# Top_Level.net
KiCad netlist of a schematic drawn in Altium Designer
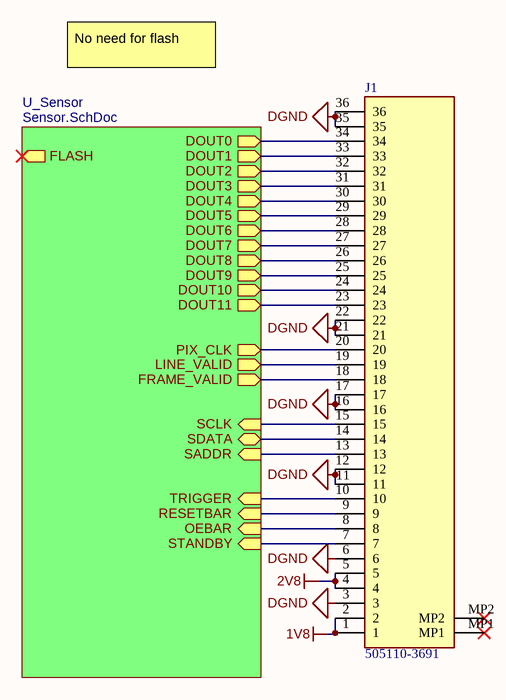
[diagram p0: Top Level.SchDoc]

(export (version "E")
  (design (tool "Eeschema 10.0.6"))
  (components
    (comp (ref "J1")
      (value "505110-3691")
      (footprint "C2Sv0.1:5051103691")
      (description "Connector")
      (libsource (lib "*") (part "505110-3691"))
    )
  )
  (nets
    (net (code "1") (name "/DOUT0") (class "Default")
      (node (ref "J1") (pin "34") (pinfunction "34_34") (pintype "passive"))
    )
    (net (code "2") (name "/DOUT1") (class "Default")
      (node (ref "J1") (pin "33") (pinfunction "33_33") (pintype "passive"))
    )
    (net (code "3") (name "/DOUT2") (class "Default")
      (node (ref "J1") (pin "32") (pinfunction "32_32") (pintype "passive"))
    )
    (net (code "4") (name "/DOUT3") (class "Default")
      (node (ref "J1") (pin "31") (pinfunction "31_31") (pintype "passive"))
    )
    (net (code "5") (name "/DOUT4") (class "Default")
      (node (ref "J1") (pin "30") (pinfunction "30_30") (pintype "passive"))
    )
    (net (code "6") (name "/DOUT5") (class "Default")
      (node (ref "J1") (pin "29") (pinfunction "29_29") (pintype "passive"))
    )
    (net (code "7") (name "/DOUT6") (class "Default")
      (node (ref "J1") (pin "28") (pinfunction "28_28") (pintype "passive"))
    )
    (net (code "8") (name "/DOUT7") (class "Default")
      (node (ref "J1") (pin "27") (pinfunction "27_27") (pintype "passive"))
    )
    (net (code "9") (name "/DOUT8") (class "Default")
      (node (ref "J1") (pin "26") (pinfunction "26_26") (pintype "passive"))
    )
    (net (code "10") (name "/DOUT9") (class "Default")
      (node (ref "J1") (pin "25") (pinfunction "25_25") (pintype "passive"))
    )
    (net (code "11") (name "/DOUT10") (class "Default")
      (node (ref "J1") (pin "24") (pinfunction "24_24") (pintype "passive"))
    )
    (net (code "12") (name "/DOUT11") (class "Default")
      (node (ref "J1") (pin "23") (pinfunction "23_23") (pintype "passive"))
    )
    (net (code "14") (name "/FRAME_VALID") (class "Default")
      (node (ref "J1") (pin "18") (pinfunction "18_18") (pintype "passive"))
    )
    (net (code "15") (name "/LINE_VALID") (class "Default")
      (node (ref "J1") (pin "19") (pinfunction "19_19") (pintype "passive"))
    )
    (net (code "16") (name "/OEBAR") (class "Default")
      (node (ref "J1") (pin "8") (pinfunction "8_8") (pintype "passive"))
    )
    (net (code "17") (name "/PIX_CLK") (class "Default")
      (node (ref "J1") (pin "20") (pinfunction "20_20") (pintype "passive"))
    )
    (net (code "18") (name "/RESETBAR") (class "Default")
      (node (ref "J1") (pin "9") (pinfunction "9_9") (pintype "passive"))
    )
    (net (code "19") (name "/SADDR") (class "Default")
      (node (ref "J1") (pin "13") (pinfunction "13_13") (pintype "passive"))
    )
    (net (code "20") (name "/SCLK") (class "Default")
      (node (ref "J1") (pin "15") (pinfunction "15_15") (pintype "passive"))
    )
    (net (code "21") (name "/SDATA") (class "Default")
      (node (ref "J1") (pin "14") (pinfunction "14_14") (pintype "passive"))
    )
    (net (code "22") (name "/STANDBY") (class "Default")
      (node (ref "J1") (pin "7") (pinfunction "7_7") (pintype "passive"))
    )
    (net (code "23") (name "/TRIGGER") (class "Default")
      (node (ref "J1") (pin "10") (pinfunction "10_10") (pintype "passive"))
    )
    (net (code "24") (name "1V8") (class "Default")
      (node (ref "J1") (pin "1") (pinfunction "1_1") (pintype "passive"))
      (node (ref "J1") (pin "2") (pinfunction "2_2") (pintype "passive"))
    )
    (net (code "25") (name "2V8") (class "Default")
      (node (ref "J1") (pin "4") (pinfunction "4_4") (pintype "passive"))
      (node (ref "J1") (pin "5") (pinfunction "5_5") (pintype "passive"))
    )
    (net (code "26") (name "DGND") (class "Default")
      (node (ref "J1") (pin "11") (pinfunction "11_11") (pintype "passive"))
      (node (ref "J1") (pin "12") (pinfunction "12_12") (pintype "passive"))
      (node (ref "J1") (pin "16") (pinfunction "16_16") (pintype "passive"))
      (node (ref "J1") (pin "17") (pinfunction "17_17") (pintype "passive"))
      (node (ref "J1") (pin "21") (pinfunction "21_21") (pintype "passive"))
      (node (ref "J1") (pin "22") (pinfunction "22_22") (pintype "passive"))
      (node (ref "J1") (pin "3") (pinfunction "3_3") (pintype "passive"))
      (node (ref "J1") (pin "35") (pinfunction "35_35") (pintype "passive"))
      (node (ref "J1") (pin "36") (pinfunction "36_36") (pintype "passive"))
      (node (ref "J1") (pin "6") (pinfunction "6_6") (pintype "passive"))
    )
    (net (code "27") (name "unconnected-(J1-PadMP1)") (class "Default")
      (node (ref "J1") (pin "MP1") (pinfunction "MP1_MP1") (pintype "passive+no_connect"))
    )
    (net (code "28") (name "unconnected-(J1-PadMP2)") (class "Default")
      (node (ref "J1") (pin "MP2") (pinfunction "MP2_MP2") (pintype "passive+no_connect"))
    )
  )
)
